# nas_control_v1.net
KiCad netlist of a schematic drawn in EAGLE
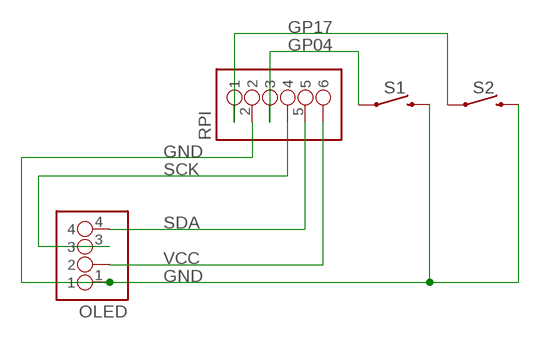
[diagram p0: schematic, sheet 1]

(export (version "E")
  (design (tool "Eeschema 10.0.6"))
  (components
    (comp (ref "OLED")
      (value "PINHD-1X04_1X04M")
      (footprint "eagle-import:1X04")
      (libsource (lib "eagle-import") (part "PINHD-1X04_1X04M"))
    )
    (comp (ref "RPI")
      (value "PINHD-1X06_1X06M")
      (footprint "eagle-import:1X06")
      (libsource (lib "eagle-import") (part "PINHD-1X06_1X06M"))
    )
    (comp (ref "S1")
      (value "MOMENTARY-SWITCH-SPST-PTH-6.0MM")
      (footprint "eagle-import:TACTILE_SWITCH_PTH_6.0MM")
      (libsource (lib "eagle-import") (part "MOMENTARY-SWITCH-SPST-PTH-6.0MM"))
    )
    (comp (ref "S2")
      (value "MOMENTARY-SWITCH-SPST-PTH-6.0MM")
      (footprint "eagle-import:TACTILE_SWITCH_PTH_6.0MM")
      (libsource (lib "eagle-import") (part "MOMENTARY-SWITCH-SPST-PTH-6.0MM"))
    )
  )
  (nets
    (net (code "1") (name "/GND") (class "Default")
      (node (ref "OLED") (pin "1") (pinfunction "1_1") (pintype "bidirectional"))
      (node (ref "RPI") (pin "2") (pinfunction "2_2") (pintype "bidirectional"))
      (node (ref "S1") (pin "3") (pinfunction "2_3") (pintype "passive"))
      (node (ref "S2") (pin "3") (pinfunction "2_3") (pintype "passive"))
    )
    (net (code "2") (name "/GP04") (class "Default")
      (node (ref "RPI") (pin "3") (pinfunction "3_3") (pintype "bidirectional"))
      (node (ref "S1") (pin "1") (pinfunction "1_1") (pintype "passive"))
    )
    (net (code "3") (name "/GP17") (class "Default")
      (node (ref "RPI") (pin "1") (pinfunction "1_1") (pintype "bidirectional"))
      (node (ref "S2") (pin "1") (pinfunction "1_1") (pintype "passive"))
    )
    (net (code "4") (name "/SCK") (class "Default")
      (node (ref "OLED") (pin "3") (pinfunction "3_3") (pintype "bidirectional"))
      (node (ref "RPI") (pin "4") (pinfunction "4_4") (pintype "bidirectional"))
    )
    (net (code "5") (name "/SDA") (class "Default")
      (node (ref "OLED") (pin "4") (pinfunction "4_4") (pintype "bidirectional"))
      (node (ref "RPI") (pin "5") (pinfunction "5_5") (pintype "bidirectional"))
    )
    (net (code "6") (name "/VCC") (class "Default")
      (node (ref "OLED") (pin "2") (pinfunction "2_2") (pintype "bidirectional"))
      (node (ref "RPI") (pin "6") (pinfunction "6_6") (pintype "bidirectional"))
    )
  )
)
